# Bop-It.net
KiCad netlist of a schematic drawn in Altium Designer
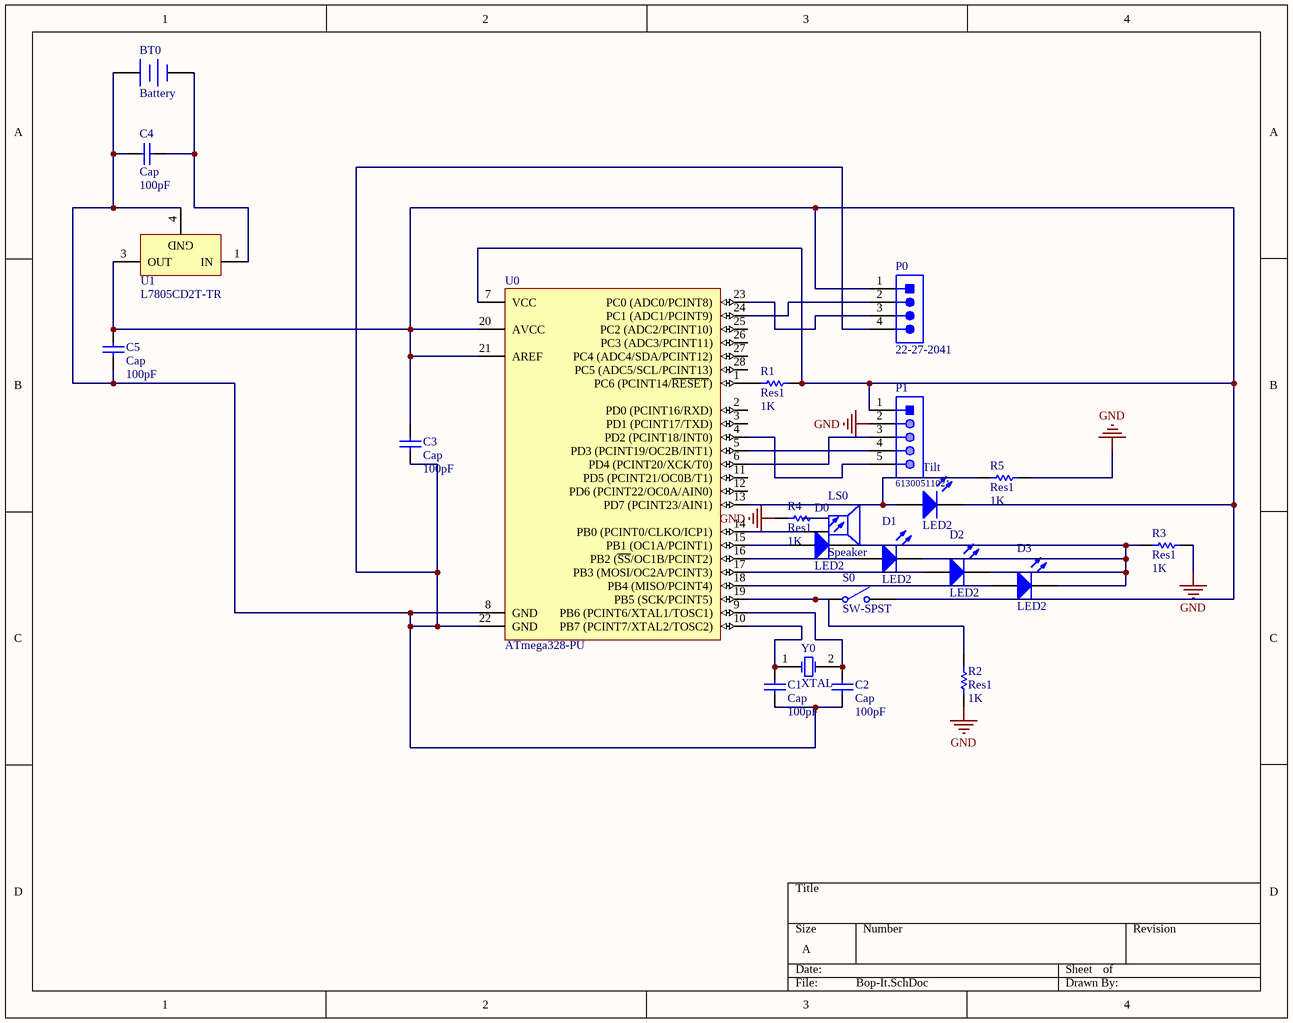
[diagram p0: Bop-It.SchDoc]

(export (version "E")
  (design (tool "Eeschema 10.0.6"))
  (components
    (comp (ref "BT0")
      (value "Battery")
      (footprint "BAT-2")
      (description "Multicell Battery")
      (fields (field (name "PUBLISHER") "Altium Limited"))
      (libsource (lib "Miscellaneous Devices") (part "Battery"))
    )
    (comp (ref "C1")
      (value "Cap")
      (footprint "RAD-0.3")
      (description "Capacitor")
      (fields (field (name "ALTIUM_VALUE") "100pF") (field (name "PUBLISHER") "Altium Limited"))
      (libsource (lib "Miscellaneous Devices") (part "Cap"))
    )
    (comp (ref "C2")
      (value "Cap")
      (footprint "RAD-0.3")
      (description "Capacitor")
      (fields (field (name "ALTIUM_VALUE") "100pF") (field (name "PUBLISHER") "Altium Limited"))
      (libsource (lib "Miscellaneous Devices") (part "Cap"))
    )
    (comp (ref "C3")
      (value "Cap")
      (footprint "RAD-0.3")
      (description "Capacitor")
      (fields (field (name "ALTIUM_VALUE") "100pF") (field (name "PUBLISHER") "Altium Limited"))
      (libsource (lib "Miscellaneous Devices") (part "Cap"))
    )
    (comp (ref "C4")
      (value "Cap")
      (footprint "RAD-0.3")
      (description "Capacitor")
      (fields (field (name "ALTIUM_VALUE") "100pF") (field (name "PUBLISHER") "Altium Limited"))
      (libsource (lib "Miscellaneous Devices") (part "Cap"))
    )
    (comp (ref "C5")
      (value "Cap")
      (footprint "RAD-0.3")
      (description "Capacitor")
      (fields (field (name "ALTIUM_VALUE") "100pF") (field (name "PUBLISHER") "Altium Limited"))
      (libsource (lib "Miscellaneous Devices") (part "Cap"))
    )
    (comp (ref "D0")
      (value "LED2")
      (footprint "3.2X1.6X1.1")
      (description "Typical RED, GREEN, YELLOW, AMBER GaAs LED")
      (fields (field (name "PUBLISHER") "Altium Limited"))
      (libsource (lib "Miscellaneous Devices") (part "LED2"))
    )
    (comp (ref "D1")
      (value "LED2")
      (footprint "3.2X1.6X1.1")
      (description "Typical RED, GREEN, YELLOW, AMBER GaAs LED")
      (fields (field (name "PUBLISHER") "Altium Limited"))
      (libsource (lib "Miscellaneous Devices") (part "LED2"))
    )
    (comp (ref "D2")
      (value "LED2")
      (footprint "3.2X1.6X1.1")
      (description "Typical RED, GREEN, YELLOW, AMBER GaAs LED")
      (fields (field (name "PUBLISHER") "Altium Limited"))
      (libsource (lib "Miscellaneous Devices") (part "LED2"))
    )
    (comp (ref "D3")
      (value "LED2")
      (footprint "3.2X1.6X1.1")
      (description "Typical RED, GREEN, YELLOW, AMBER GaAs LED")
      (fields (field (name "PUBLISHER") "Altium Limited"))
      (libsource (lib "Miscellaneous Devices") (part "LED2"))
    )
    (comp (ref "LS0")
      (value "Speaker")
      (footprint "PIN2")
      (description "Loudspeaker")
      (fields (field (name "PUBLISHER") "Altium Limited"))
      (libsource (lib "Miscellaneous Devices") (part "Speaker"))
    )
    (comp (ref "P0")
      (value "22-27-2041")
      (footprint "MOLX-22-27-2041_V")
      (description "Male Header, Pitch 2.54 mm, 1 x 4 Position, Height 11.7 mm, Tail Length 3.56 mm, RoHS, Bulk")
      (fields (field (name "MANUFACTURER") "Molex"))
      (libsource (lib "Altium Content Vault") (part "CN-1P-M-R4"))
    )
    (comp (ref "P1")
      (value "61300511021")
      (footprint "61300511021")
      (description "THT Angled Pin Header WR-PHD, Pitch 2.54 mm, Single Row, 5 pins")
      (fields (field (name "MANUFACTURER") "Wurth Elektronik") (field (name "PUBLISHER") "WurthElektronik"))
      (libsource (lib "Altium Content Vault") (part "WE-CN-1P-M-R5"))
    )
    (comp (ref "R1")
      (value "Res1")
      (footprint "AXIAL-0.3")
      (description "Resistor")
      (fields (field (name "ALTIUM_VALUE") "1K") (field (name "PUBLISHER") "Altium Limited"))
      (libsource (lib "Miscellaneous Devices") (part "Res1"))
    )
    (comp (ref "R2")
      (value "Res1")
      (footprint "AXIAL-0.3")
      (description "Resistor")
      (fields (field (name "ALTIUM_VALUE") "1K") (field (name "PUBLISHER") "Altium Limited"))
      (libsource (lib "Miscellaneous Devices") (part "Res1"))
    )
    (comp (ref "R3")
      (value "Res1")
      (footprint "AXIAL-0.3")
      (description "Resistor")
      (fields (field (name "ALTIUM_VALUE") "1K") (field (name "PUBLISHER") "Altium Limited"))
      (libsource (lib "Miscellaneous Devices") (part "Res1"))
    )
    (comp (ref "R4")
      (value "Res1")
      (footprint "AXIAL-0.3")
      (description "Resistor")
      (fields (field (name "ALTIUM_VALUE") "1K") (field (name "PUBLISHER") "Altium Limited"))
      (libsource (lib "Miscellaneous Devices") (part "Res1"))
    )
    (comp (ref "R5")
      (value "Res1")
      (footprint "AXIAL-0.3")
      (description "Resistor")
      (fields (field (name "ALTIUM_VALUE") "1K") (field (name "PUBLISHER") "Altium Limited"))
      (libsource (lib "Miscellaneous Devices") (part "Res1"))
    )
    (comp (ref "S0")
      (value "SW-SPST")
      (footprint "SPST-2")
      (description "Single-Pole, Single-Throw Switch")
      (fields (field (name "PUBLISHER") "Altium Limited"))
      (libsource (lib "Miscellaneous Devices") (part "SW-SPST"))
    )
    (comp (ref "Tilt")
      (value "LED2")
      (footprint "3.2X1.6X1.1")
      (description "Typical RED, GREEN, YELLOW, AMBER GaAs LED")
      (fields (field (name "PUBLISHER") "Altium Limited"))
      (libsource (lib "Miscellaneous Devices") (part "LED2"))
    )
    (comp (ref "U0")
      (value "ATmega328-PU")
      (footprint "28P3")
      (libsource (lib "Altium Content Vault") (part "MC-8B-ATM48-IL28"))
    )
    (comp (ref "U1")
      (value "L7805CD2T-TR")
      (footprint "TO-263_M")
      (description "Positive Voltage Regulator, 3-Pin D2PAK, Tape and Reel")
      (libsource (lib "Altium Content Vault") (part "PM-REG-L4940-SOT3"))
    )
    (comp (ref "Y0")
      (value "XTAL")
      (footprint "R38")
      (description "Crystal Oscillator")
      (fields (field (name "PUBLISHER") "Altium Limited"))
      (libsource (lib "Miscellaneous Devices") (part "XTAL"))
    )
  )
  (nets
    (net (code "1") (name "GND") (class "Default")
      (node (ref "P1") (pin "2") (pinfunction "2_2") (pintype "passive"))
      (node (ref "R2") (pin "1") (pinfunction "1_1") (pintype "passive"))
      (node (ref "R3") (pin "2") (pinfunction "2_2") (pintype "passive"))
      (node (ref "R4") (pin "1") (pinfunction "1_1") (pintype "passive"))
      (node (ref "R5") (pin "1") (pinfunction "1_1") (pintype "passive"))
    )
    (net (code "2") (name "Net-(BT0-+)") (class "Default")
      (node (ref "BT0") (pin "1") (pinfunction "+_1") (pintype "passive"))
      (node (ref "C1") (pin "2") (pinfunction "2_2") (pintype "passive"))
      (node (ref "C2") (pin "2") (pinfunction "2_2") (pintype "passive"))
      (node (ref "C3") (pin "2") (pinfunction "2_2") (pintype "passive"))
      (node (ref "C4") (pin "1") (pinfunction "1_1") (pintype "passive"))
      (node (ref "C5") (pin "2") (pinfunction "2_2") (pintype "passive"))
      (node (ref "P0") (pin "4") (pinfunction "4_4") (pintype "passive"))
      (node (ref "U0") (pin "22") (pinfunction "GND_22") (pintype "power_in"))
      (node (ref "U0") (pin "8") (pinfunction "GND_8") (pintype "power_in"))
      (node (ref "U1") (pin "4") (pinfunction "GND_4") (pintype "power_in"))
    )
    (net (code "3") (name "Net-(BT0--)") (class "Default")
      (node (ref "BT0") (pin "2") (pinfunction "-_2") (pintype "passive"))
      (node (ref "C4") (pin "2") (pinfunction "2_2") (pintype "passive"))
      (node (ref "U1") (pin "1") (pinfunction "IN_1") (pintype "power_in"))
    )
    (net (code "4") (name "Net-(D0-A)") (class "Default")
      (node (ref "D0") (pin "1") (pinfunction "A_1") (pintype "passive"))
      (node (ref "U0") (pin "15") (pinfunction "PB1_(OC1A/PCINT1)_15") (pintype "bidirectional"))
    )
    (net (code "5") (name "Net-(D0-K)") (class "Default")
      (node (ref "D0") (pin "2") (pinfunction "K_2") (pintype "passive"))
      (node (ref "D1") (pin "2") (pinfunction "K_2") (pintype "passive"))
      (node (ref "D2") (pin "2") (pinfunction "K_2") (pintype "passive"))
      (node (ref "D3") (pin "2") (pinfunction "K_2") (pintype "passive"))
      (node (ref "R3") (pin "1") (pinfunction "1_1") (pintype "passive"))
    )
    (net (code "6") (name "Net-(D1-A)") (class "Default")
      (node (ref "D1") (pin "1") (pinfunction "A_1") (pintype "passive"))
      (node (ref "U0") (pin "16") (pinfunction "PB2_(~{SS}/OC1B/PCINT2)_16") (pintype "bidirectional"))
    )
    (net (code "7") (name "Net-(D2-A)") (class "Default")
      (node (ref "D2") (pin "1") (pinfunction "A_1") (pintype "passive"))
      (node (ref "U0") (pin "17") (pinfunction "PB3_(MOSI/OC2A/PCINT3)_17") (pintype "bidirectional"))
    )
    (net (code "8") (name "Net-(D3-A)") (class "Default")
      (node (ref "D3") (pin "1") (pinfunction "A_1") (pintype "passive"))
      (node (ref "U0") (pin "18") (pinfunction "PB4_(MISO/PCINT4)_18") (pintype "bidirectional"))
    )
    (net (code "9") (name "Net-(LS0-Pad1)") (class "Default")
      (node (ref "LS0") (pin "1") (pinfunction "1_1") (pintype "passive"))
      (node (ref "R4") (pin "2") (pinfunction "2_2") (pintype "passive"))
    )
    (net (code "10") (name "Net-(S0-COMMON)") (class "Default")
      (node (ref "R2") (pin "2") (pinfunction "2_2") (pintype "passive"))
      (node (ref "S0") (pin "1") (pinfunction "COMMON_1") (pintype "passive"))
      (node (ref "U0") (pin "19") (pinfunction "PB5_(SCK/PCINT5)_19") (pintype "bidirectional"))
    )
    (net (code "11") (name "Net-(S0-NO)") (class "Default")
      (node (ref "C3") (pin "1") (pinfunction "1_1") (pintype "passive"))
      (node (ref "C5") (pin "1") (pinfunction "1_1") (pintype "passive"))
      (node (ref "P0") (pin "1") (pinfunction "1_1") (pintype "passive"))
      (node (ref "P1") (pin "1") (pinfunction "1_1") (pintype "passive"))
      (node (ref "R1") (pin "2") (pinfunction "2_2") (pintype "passive"))
      (node (ref "S0") (pin "2") (pinfunction "NO_2") (pintype "passive"))
      (node (ref "Tilt") (pin "2") (pinfunction "K_2") (pintype "passive"))
      (node (ref "U0") (pin "20") (pinfunction "AVCC_20") (pintype "power_in"))
      (node (ref "U0") (pin "21") (pinfunction "AREF_21") (pintype "power_in"))
      (node (ref "U0") (pin "7") (pinfunction "VCC_7") (pintype "power_in"))
      (node (ref "U1") (pin "3") (pinfunction "OUT_3") (pintype "power_in"))
    )
    (net (code "12") (name "Net-(Tilt-A)") (class "Default")
      (node (ref "R5") (pin "2") (pinfunction "2_2") (pintype "passive"))
      (node (ref "Tilt") (pin "1") (pinfunction "A_1") (pintype "passive"))
      (node (ref "U0") (pin "13") (pinfunction "PD7_(PCINT23/AIN1)_13") (pintype "bidirectional"))
    )
    (net (code "13") (name "Net-(U0-PB0_(PCINT0{slash}CLKO{slash}ICP1))") (class "Default")
      (node (ref "LS0") (pin "2") (pinfunction "2_2") (pintype "passive"))
      (node (ref "U0") (pin "14") (pinfunction "PB0_(PCINT0/CLKO/ICP1)_14") (pintype "bidirectional"))
    )
    (net (code "14") (name "Net-(U0-PB6_(PCINT6{slash}XTAL1{slash}TOSC1))") (class "Default")
      (node (ref "C2") (pin "1") (pinfunction "1_1") (pintype "passive"))
      (node (ref "U0") (pin "9") (pinfunction "PB6_(PCINT6/XTAL1/TOSC1)_9") (pintype "bidirectional"))
      (node (ref "Y0") (pin "2") (pinfunction "OSC2_2") (pintype "passive"))
    )
    (net (code "15") (name "Net-(U0-PB7_(PCINT7{slash}XTAL2{slash}TOSC2))") (class "Default")
      (node (ref "C1") (pin "1") (pinfunction "1_1") (pintype "passive"))
      (node (ref "U0") (pin "10") (pinfunction "PB7_(PCINT7/XTAL2/TOSC2)_10") (pintype "bidirectional"))
      (node (ref "Y0") (pin "1") (pinfunction "OSC1_1") (pintype "passive"))
    )
    (net (code "16") (name "Net-(U0-PC0_(ADC0{slash}PCINT8))") (class "Default")
      (node (ref "P0") (pin "3") (pinfunction "3_3") (pintype "passive"))
      (node (ref "U0") (pin "23") (pinfunction "PC0_(ADC0/PCINT8)_23") (pintype "bidirectional"))
    )
    (net (code "17") (name "Net-(U0-PC1_(ADC1{slash}PCINT9))") (class "Default")
      (node (ref "P0") (pin "2") (pinfunction "2_2") (pintype "passive"))
      (node (ref "U0") (pin "24") (pinfunction "PC1_(ADC1/PCINT9)_24") (pintype "bidirectional"))
    )
    (net (code "18") (name "Net-(U0-PC6_(PCINT14{slash}~{RESET}))") (class "Default")
      (node (ref "R1") (pin "1") (pinfunction "1_1") (pintype "passive"))
      (node (ref "U0") (pin "1") (pinfunction "PC6_(PCINT14/~{RESET})_1") (pintype "bidirectional"))
    )
    (net (code "19") (name "Net-(U0-PD2_(PCINT18{slash}INT0))") (class "Default")
      (node (ref "P1") (pin "5") (pinfunction "5_5") (pintype "passive"))
      (node (ref "U0") (pin "4") (pinfunction "PD2_(PCINT18/INT0)_4") (pintype "bidirectional"))
    )
    (net (code "20") (name "Net-(U0-PD3_(PCINT19{slash}OC2B{slash}INT1))") (class "Default")
      (node (ref "P1") (pin "4") (pinfunction "4_4") (pintype "passive"))
      (node (ref "U0") (pin "5") (pinfunction "PD3_(PCINT19/OC2B/INT1)_5") (pintype "bidirectional"))
    )
    (net (code "21") (name "Net-(U0-PD4_(PCINT20{slash}XCK{slash}T0))") (class "Default")
      (node (ref "P1") (pin "3") (pinfunction "3_3") (pintype "passive"))
      (node (ref "U0") (pin "6") (pinfunction "PD4_(PCINT20/XCK/T0)_6") (pintype "bidirectional"))
    )
    (net (code "22") (name "unconnected-(U0-PC2_(ADC2{slash}PCINT10)-Pad25)") (class "Default")
      (node (ref "U0") (pin "25") (pinfunction "PC2_(ADC2/PCINT10)_25") (pintype "bidirectional"))
    )
    (net (code "23") (name "unconnected-(U0-PC3_(ADC3{slash}PCINT11)-Pad26)") (class "Default")
      (node (ref "U0") (pin "26") (pinfunction "PC3_(ADC3/PCINT11)_26") (pintype "bidirectional"))
    )
    (net (code "24") (name "unconnected-(U0-PC4_(ADC4{slash}SDA{slash}PCINT12)-Pad27)") (class "Default")
      (node (ref "U0") (pin "27") (pinfunction "PC4_(ADC4/SDA/PCINT12)_27") (pintype "bidirectional"))
    )
    (net (code "25") (name "unconnected-(U0-PC5_(ADC5{slash}SCL{slash}PCINT13)-Pad28)") (class "Default")
      (node (ref "U0") (pin "28") (pinfunction "PC5_(ADC5/SCL/PCINT13)_28") (pintype "bidirectional"))
    )
    (net (code "26") (name "unconnected-(U0-PD0_(PCINT16{slash}RXD)-Pad2)") (class "Default")
      (node (ref "U0") (pin "2") (pinfunction "PD0_(PCINT16/RXD)_2") (pintype "bidirectional"))
    )
    (net (code "27") (name "unconnected-(U0-PD1_(PCINT17{slash}TXD)-Pad3)") (class "Default")
      (node (ref "U0") (pin "3") (pinfunction "PD1_(PCINT17/TXD)_3") (pintype "bidirectional"))
    )
    (net (code "28") (name "unconnected-(U0-PD5_(PCINT21{slash}OC0B{slash}T1)-Pad11)") (class "Default")
      (node (ref "U0") (pin "11") (pinfunction "PD5_(PCINT21/OC0B/T1)_11") (pintype "bidirectional"))
    )
    (net (code "29") (name "unconnected-(U0-PD6_(PCINT22{slash}OC0A{slash}AIN0)-Pad12)") (class "Default")
      (node (ref "U0") (pin "12") (pinfunction "PD6_(PCINT22/OC0A/AIN0)_12") (pintype "bidirectional"))
    )
  )
)
